# main.net
KiCad netlist of a schematic drawn in EAGLE
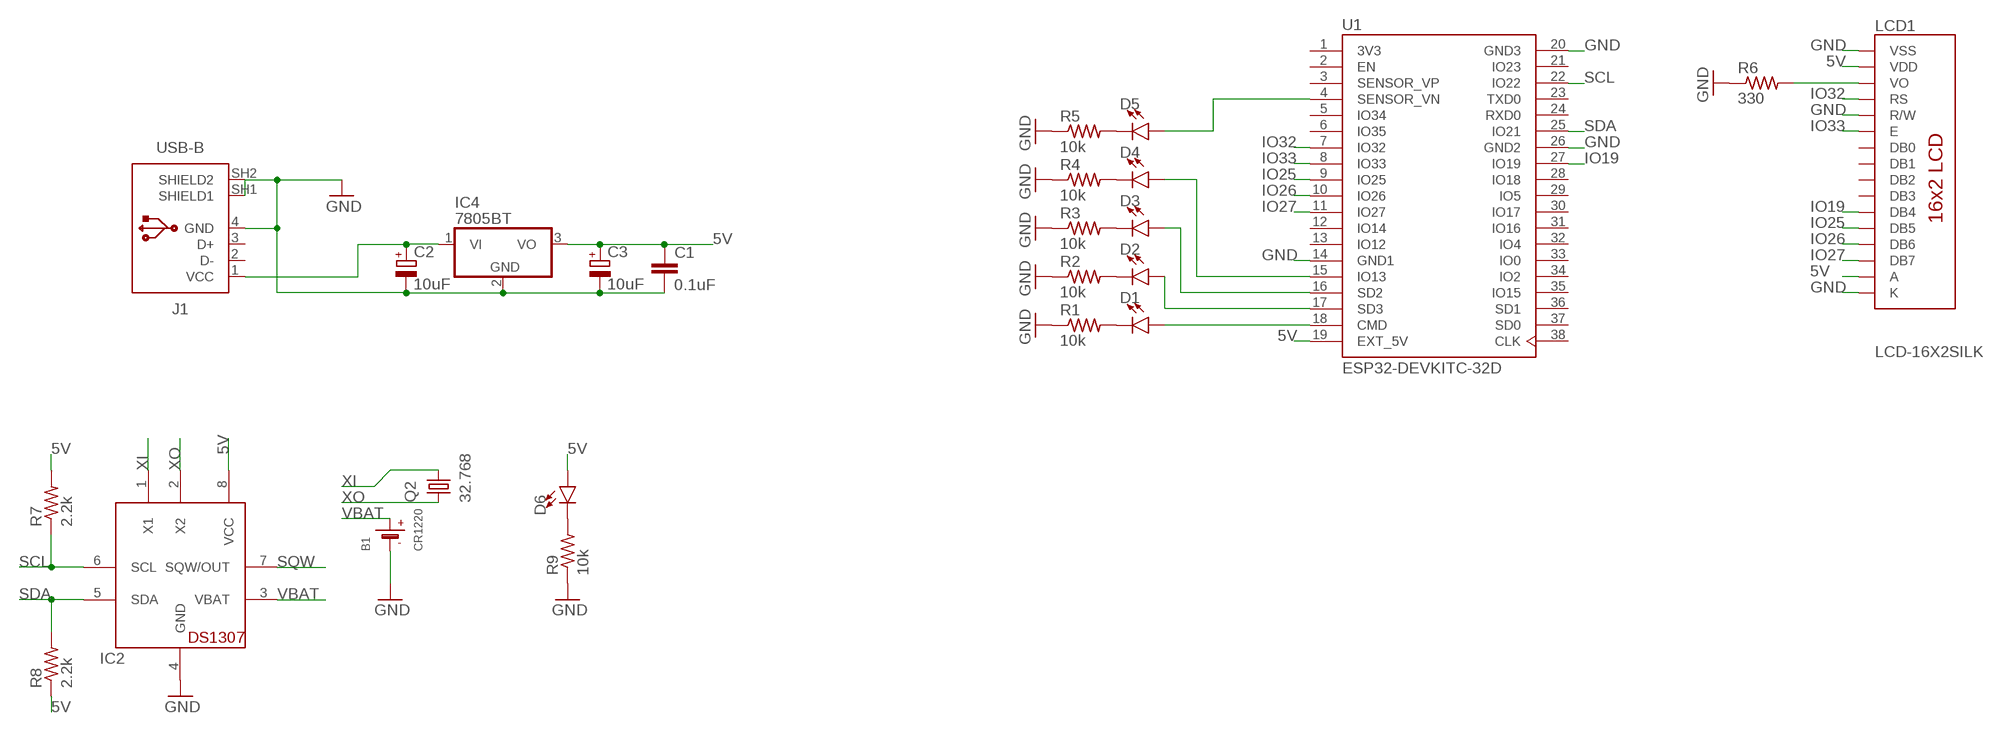
[diagram p0: schematic, sheet 1]

(export (version "E")
  (design (tool "Eeschema 10.0.6"))
  (components
    (comp (ref "B1")
      (value "CR1220")
      (footprint "eagle-import:CR1220")
      (libsource (lib "eagle-import") (part "BATTERYCR1220_SMT"))
    )
    (comp (ref "C1")
      (value "0.1uF")
      (footprint "eagle-import:C050-024X044")
      (libsource (lib "eagle-import") (part "C-EU050-024X044"))
    )
    (comp (ref "C2")
      (value "10uF")
      (footprint "eagle-import:E2-5")
      (libsource (lib "eagle-import") (part "CPOL-EUE2-5"))
    )
    (comp (ref "C3")
      (value "10uF")
      (footprint "eagle-import:E2-5")
      (libsource (lib "eagle-import") (part "CPOL-EUE2-5"))
    )
    (comp (ref "D1")
      (value "LED5MM")
      (footprint "eagle-import:LED_5MM")
      (libsource (lib "eagle-import") (part "LED5MM"))
    )
    (comp (ref "D2")
      (value "LED5MM")
      (footprint "eagle-import:LED_5MM")
      (libsource (lib "eagle-import") (part "LED5MM"))
    )
    (comp (ref "D3")
      (value "LED5MM")
      (footprint "eagle-import:LED_5MM")
      (libsource (lib "eagle-import") (part "LED5MM"))
    )
    (comp (ref "D4")
      (value "LED5MM")
      (footprint "eagle-import:LED_5MM")
      (libsource (lib "eagle-import") (part "LED5MM"))
    )
    (comp (ref "D5")
      (value "LED5MM")
      (footprint "eagle-import:LED_5MM")
      (libsource (lib "eagle-import") (part "LED5MM"))
    )
    (comp (ref "D6")
      (value "LED5MM")
      (footprint "eagle-import:LED_5MM")
      (libsource (lib "eagle-import") (part "LED5MM"))
    )
    (comp (ref "IC2")
      (value "DS1307")
      (footprint "eagle-import:DIL08")
      (libsource (lib "eagle-import") (part "DS1307"))
    )
    (comp (ref "IC4")
      (value "7805BT")
      (footprint "eagle-import:TO220V")
      (libsource (lib "eagle-import") (part "78TV05"))
    )
    (comp (ref "J1")
      (value "USB-B")
      (footprint "eagle-import:61729-1011BLF")
      (fields (field (name "MANUFACTURER") "Amphenol ICC (FCI)") (field (name "MPN") "61729-1011BLF"))
      (libsource (lib "eagle-import") (part "61729-1011"))
    )
    (comp (ref "LCD1")
      (value "LCD-16X2SILK")
      (footprint "eagle-import:LCD-16X2")
      (libsource (lib "eagle-import") (part "LCD-16X2SILK"))
    )
    (comp (ref "Q2")
      (value "32.768")
      (footprint "eagle-import:TC26V")
      (libsource (lib "eagle-import") (part "CRYSTALTC26V"))
    )
    (comp (ref "R1")
      (value "10k")
      (footprint "eagle-import:0207_7")
      (libsource (lib "eagle-import") (part "R-US_0207/7"))
    )
    (comp (ref "R2")
      (value "10k")
      (footprint "eagle-import:0207_7")
      (libsource (lib "eagle-import") (part "R-US_0207/7"))
    )
    (comp (ref "R3")
      (value "10k")
      (footprint "eagle-import:0207_7")
      (libsource (lib "eagle-import") (part "R-US_0207/7"))
    )
    (comp (ref "R4")
      (value "10k")
      (footprint "eagle-import:0207_7")
      (libsource (lib "eagle-import") (part "R-US_0207/7"))
    )
    (comp (ref "R5")
      (value "10k")
      (footprint "eagle-import:0207_7")
      (libsource (lib "eagle-import") (part "R-US_0207/7"))
    )
    (comp (ref "R6")
      (value "330")
      (footprint "eagle-import:0207_7")
      (libsource (lib "eagle-import") (part "R-US_0207/7"))
    )
    (comp (ref "R7")
      (value "2.2k")
      (footprint "eagle-import:0207_7")
      (libsource (lib "eagle-import") (part "R-US_0207/7"))
    )
    (comp (ref "R8")
      (value "2.2k")
      (footprint "eagle-import:0207_7")
      (libsource (lib "eagle-import") (part "R-US_0207/7"))
    )
    (comp (ref "R9")
      (value "10k")
      (footprint "eagle-import:0207_7")
      (libsource (lib "eagle-import") (part "R-US_0207/7"))
    )
    (comp (ref "U1")
      (value "ESP32-DEVKITC-32D")
      (footprint "eagle-import:MODULE_ESP32-DEVKITC-32D")
      (fields (field (name "MF") "Espressif Systems"))
      (libsource (lib "eagle-import") (part "ESP32-DEVKITC-32D"))
    )
  )
  (nets
    (net (code "1") (name "/3V3") (class "Default")
      (node (ref "U1") (pin "1") (pinfunction "3V3_1") (pintype "power_in"))
    )
    (net (code "2") (name "/5V") (class "Default")
      (node (ref "C1") (pin "1") (pinfunction "1_1") (pintype "passive"))
      (node (ref "C3") (pin "+") (pinfunction "+_+") (pintype "passive"))
      (node (ref "D6") (pin "A") (pinfunction "A_A") (pintype "passive"))
      (node (ref "IC2") (pin "8") (pinfunction "VCC_8") (pintype "power_in"))
      (node (ref "IC4") (pin "3") (pinfunction "VO_3") (pintype "passive"))
      (node (ref "LCD1") (pin "15") (pinfunction "A_15") (pintype "power_in"))
      (node (ref "LCD1") (pin "2") (pinfunction "VDD_2") (pintype "power_in"))
      (node (ref "R7") (pin "2") (pinfunction "2_2") (pintype "passive"))
      (node (ref "R8") (pin "1") (pinfunction "1_1") (pintype "passive"))
      (node (ref "U1") (pin "19") (pinfunction "EXT_5V_19") (pintype "power_in"))
    )
    (net (code "3") (name "/IO19") (class "Default")
      (node (ref "LCD1") (pin "11") (pinfunction "DB4_11") (pintype "bidirectional"))
      (node (ref "U1") (pin "27") (pinfunction "IO19_27") (pintype "bidirectional"))
    )
    (net (code "4") (name "/IO25") (class "Default")
      (node (ref "LCD1") (pin "12") (pinfunction "DB5_12") (pintype "bidirectional"))
      (node (ref "U1") (pin "9") (pinfunction "IO25_9") (pintype "bidirectional"))
    )
    (net (code "5") (name "/IO26") (class "Default")
      (node (ref "LCD1") (pin "13") (pinfunction "DB6_13") (pintype "bidirectional"))
      (node (ref "U1") (pin "10") (pinfunction "IO26_10") (pintype "bidirectional"))
    )
    (net (code "6") (name "/IO27") (class "Default")
      (node (ref "LCD1") (pin "14") (pinfunction "DB7_14") (pintype "bidirectional"))
      (node (ref "U1") (pin "11") (pinfunction "IO27_11") (pintype "bidirectional"))
    )
    (net (code "7") (name "/IO32") (class "Default")
      (node (ref "LCD1") (pin "4") (pinfunction "RS_4") (pintype "input"))
      (node (ref "U1") (pin "7") (pinfunction "IO32_7") (pintype "bidirectional"))
    )
    (net (code "8") (name "/IO33") (class "Default")
      (node (ref "LCD1") (pin "6") (pinfunction "E_6") (pintype "input"))
      (node (ref "U1") (pin "8") (pinfunction "IO33_8") (pintype "bidirectional"))
    )
    (net (code "9") (name "/SCL") (class "Default")
      (node (ref "IC2") (pin "6") (pinfunction "SCL_6") (pintype "bidirectional"))
      (node (ref "R7") (pin "1") (pinfunction "1_1") (pintype "passive"))
      (node (ref "U1") (pin "22") (pinfunction "IO22_22") (pintype "bidirectional"))
    )
    (net (code "10") (name "/SDA") (class "Default")
      (node (ref "IC2") (pin "5") (pinfunction "SDA_5") (pintype "bidirectional"))
      (node (ref "R8") (pin "2") (pinfunction "2_2") (pintype "passive"))
      (node (ref "U1") (pin "25") (pinfunction "IO21_25") (pintype "bidirectional"))
    )
    (net (code "11") (name "/SQW") (class "Default")
      (node (ref "IC2") (pin "7") (pinfunction "SQW/OUT_7") (pintype "bidirectional"))
    )
    (net (code "12") (name "/VBAT") (class "Default")
      (node (ref "B1") (pin "+$1") (pinfunction "+_+$1") (pintype "passive"))
      (node (ref "IC2") (pin "3") (pinfunction "VBAT_3") (pintype "power_in"))
    )
    (net (code "13") (name "/XI") (class "Default")
      (node (ref "IC2") (pin "1") (pinfunction "X1_1") (pintype "passive"))
      (node (ref "Q2") (pin "2") (pinfunction "2_2") (pintype "passive"))
    )
    (net (code "14") (name "/XO") (class "Default")
      (node (ref "IC2") (pin "2") (pinfunction "X2_2") (pintype "passive"))
      (node (ref "Q2") (pin "1") (pinfunction "1_1") (pintype "passive"))
    )
    (net (code "15") (name "GND") (class "Default")
      (node (ref "B1") (pin "-") (pinfunction "-_-") (pintype "passive"))
      (node (ref "C1") (pin "2") (pinfunction "2_2") (pintype "passive"))
      (node (ref "C2") (pin "-") (pinfunction "-_-") (pintype "passive"))
      (node (ref "C3") (pin "-") (pinfunction "-_-") (pintype "passive"))
      (node (ref "IC2") (pin "4") (pinfunction "GND_4") (pintype "power_in"))
      (node (ref "IC4") (pin "2") (pinfunction "GND_2") (pintype "passive"))
      (node (ref "J1") (pin "4") (pinfunction "GND_4") (pintype "power_in"))
      (node (ref "J1") (pin "SH1") (pinfunction "SHIELD1_SH1") (pintype "power_in"))
      (node (ref "J1") (pin "SH2") (pinfunction "SHIELD2_SH2") (pintype "power_in"))
      (node (ref "LCD1") (pin "1") (pinfunction "VSS_1") (pintype "power_in"))
      (node (ref "LCD1") (pin "16") (pinfunction "K_16") (pintype "power_in"))
      (node (ref "LCD1") (pin "5") (pinfunction "R/W_5") (pintype "input"))
      (node (ref "R1") (pin "1") (pinfunction "1_1") (pintype "passive"))
      (node (ref "R2") (pin "1") (pinfunction "1_1") (pintype "passive"))
      (node (ref "R3") (pin "1") (pinfunction "1_1") (pintype "passive"))
      (node (ref "R4") (pin "1") (pinfunction "1_1") (pintype "passive"))
      (node (ref "R5") (pin "1") (pinfunction "1_1") (pintype "passive"))
      (node (ref "R6") (pin "1") (pinfunction "1_1") (pintype "passive"))
      (node (ref "R9") (pin "1") (pinfunction "1_1") (pintype "passive"))
      (node (ref "U1") (pin "14") (pinfunction "GND1_14") (pintype "power_in"))
      (node (ref "U1") (pin "20") (pinfunction "GND3_20") (pintype "power_in"))
      (node (ref "U1") (pin "26") (pinfunction "GND2_26") (pintype "power_in"))
    )
    (net (code "16") (name "Net-(D1-C)") (class "Default")
      (node (ref "D1") (pin "K") (pinfunction "C_K") (pintype "passive"))
      (node (ref "R1") (pin "2") (pinfunction "2_2") (pintype "passive"))
    )
    (net (code "17") (name "Net-(D2-C)") (class "Default")
      (node (ref "D2") (pin "K") (pinfunction "C_K") (pintype "passive"))
      (node (ref "R2") (pin "2") (pinfunction "2_2") (pintype "passive"))
    )
    (net (code "18") (name "Net-(D3-C)") (class "Default")
      (node (ref "D3") (pin "K") (pinfunction "C_K") (pintype "passive"))
      (node (ref "R3") (pin "2") (pinfunction "2_2") (pintype "passive"))
    )
    (net (code "19") (name "Net-(D4-C)") (class "Default")
      (node (ref "D4") (pin "K") (pinfunction "C_K") (pintype "passive"))
      (node (ref "R4") (pin "2") (pinfunction "2_2") (pintype "passive"))
    )
    (net (code "20") (name "Net-(D5-C)") (class "Default")
      (node (ref "D5") (pin "K") (pinfunction "C_K") (pintype "passive"))
      (node (ref "R5") (pin "2") (pinfunction "2_2") (pintype "passive"))
    )
    (net (code "21") (name "Net-(D6-C)") (class "Default")
      (node (ref "D6") (pin "K") (pinfunction "C_K") (pintype "passive"))
      (node (ref "R9") (pin "2") (pinfunction "2_2") (pintype "passive"))
    )
    (net (code "22") (name "Net-(IC4-VI)") (class "Default")
      (node (ref "C2") (pin "+") (pinfunction "+_+") (pintype "passive"))
      (node (ref "IC4") (pin "1") (pinfunction "VI_1") (pintype "input"))
      (node (ref "J1") (pin "1") (pinfunction "VCC_1") (pintype "power_in"))
    )
    (net (code "23") (name "Net-(LCD1-VO)") (class "Default")
      (node (ref "LCD1") (pin "3") (pinfunction "VO_3") (pintype "bidirectional"))
      (node (ref "R6") (pin "2") (pinfunction "2_2") (pintype "passive"))
    )
    (net (code "24") (name "Net-(U1-CMD)") (class "Default")
      (node (ref "D1") (pin "A") (pinfunction "A_A") (pintype "passive"))
      (node (ref "U1") (pin "18") (pinfunction "CMD_18") (pintype "bidirectional"))
    )
    (net (code "25") (name "Net-(U1-IO13)") (class "Default")
      (node (ref "D4") (pin "A") (pinfunction "A_A") (pintype "passive"))
      (node (ref "U1") (pin "15") (pinfunction "IO13_15") (pintype "bidirectional"))
    )
    (net (code "26") (name "Net-(U1-SD2)") (class "Default")
      (node (ref "D3") (pin "A") (pinfunction "A_A") (pintype "passive"))
      (node (ref "U1") (pin "16") (pinfunction "SD2_16") (pintype "bidirectional"))
    )
    (net (code "27") (name "Net-(U1-SD3)") (class "Default")
      (node (ref "D2") (pin "A") (pinfunction "A_A") (pintype "passive"))
      (node (ref "U1") (pin "17") (pinfunction "SD3_17") (pintype "bidirectional"))
    )
    (net (code "28") (name "Net-(U1-SENSOR_VN)") (class "Default")
      (node (ref "D5") (pin "A") (pinfunction "A_A") (pintype "passive"))
      (node (ref "U1") (pin "4") (pinfunction "SENSOR_VN_4") (pintype "input"))
    )
    (net (code "29") (name "unconnected-(J1-D+-Pad3)") (class "Default")
      (node (ref "J1") (pin "3") (pinfunction "D+_3") (pintype "bidirectional"))
    )
    (net (code "30") (name "unconnected-(J1-D--Pad2)") (class "Default")
      (node (ref "J1") (pin "2") (pinfunction "D-_2") (pintype "bidirectional"))
    )
    (net (code "31") (name "unconnected-(LCD1-DB0-Pad7)") (class "Default")
      (node (ref "LCD1") (pin "7") (pinfunction "DB0_7") (pintype "bidirectional"))
    )
    (net (code "32") (name "unconnected-(LCD1-DB1-Pad8)") (class "Default")
      (node (ref "LCD1") (pin "8") (pinfunction "DB1_8") (pintype "bidirectional"))
    )
    (net (code "33") (name "unconnected-(LCD1-DB2-Pad9)") (class "Default")
      (node (ref "LCD1") (pin "9") (pinfunction "DB2_9") (pintype "bidirectional"))
    )
    (net (code "34") (name "unconnected-(LCD1-DB3-Pad10)") (class "Default")
      (node (ref "LCD1") (pin "10") (pinfunction "DB3_10") (pintype "bidirectional"))
    )
    (net (code "35") (name "unconnected-(U1-CLK-Pad38)") (class "Default")
      (node (ref "U1") (pin "38") (pinfunction "CLK_38") (pintype "input"))
    )
    (net (code "36") (name "unconnected-(U1-EN-Pad2)") (class "Default")
      (node (ref "U1") (pin "2") (pinfunction "EN_2") (pintype "input"))
    )
    (net (code "37") (name "unconnected-(U1-IO0-Pad33)") (class "Default")
      (node (ref "U1") (pin "33") (pinfunction "IO0_33") (pintype "bidirectional"))
    )
    (net (code "38") (name "unconnected-(U1-IO2-Pad34)") (class "Default")
      (node (ref "U1") (pin "34") (pinfunction "IO2_34") (pintype "bidirectional"))
    )
    (net (code "39") (name "unconnected-(U1-IO4-Pad32)") (class "Default")
      (node (ref "U1") (pin "32") (pinfunction "IO4_32") (pintype "bidirectional"))
    )
    (net (code "40") (name "unconnected-(U1-IO5-Pad29)") (class "Default")
      (node (ref "U1") (pin "29") (pinfunction "IO5_29") (pintype "bidirectional"))
    )
    (net (code "41") (name "unconnected-(U1-IO12-Pad13)") (class "Default")
      (node (ref "U1") (pin "13") (pinfunction "IO12_13") (pintype "bidirectional"))
    )
    (net (code "42") (name "unconnected-(U1-IO14-Pad12)") (class "Default")
      (node (ref "U1") (pin "12") (pinfunction "IO14_12") (pintype "bidirectional"))
    )
    (net (code "43") (name "unconnected-(U1-IO15-Pad35)") (class "Default")
      (node (ref "U1") (pin "35") (pinfunction "IO15_35") (pintype "bidirectional"))
    )
    (net (code "44") (name "unconnected-(U1-IO16-Pad31)") (class "Default")
      (node (ref "U1") (pin "31") (pinfunction "IO16_31") (pintype "bidirectional"))
    )
    (net (code "45") (name "unconnected-(U1-IO17-Pad30)") (class "Default")
      (node (ref "U1") (pin "30") (pinfunction "IO17_30") (pintype "bidirectional"))
    )
    (net (code "46") (name "unconnected-(U1-IO18-Pad28)") (class "Default")
      (node (ref "U1") (pin "28") (pinfunction "IO18_28") (pintype "bidirectional"))
    )
    (net (code "47") (name "unconnected-(U1-IO23-Pad21)") (class "Default")
      (node (ref "U1") (pin "21") (pinfunction "IO23_21") (pintype "bidirectional"))
    )
    (net (code "48") (name "unconnected-(U1-IO34-Pad5)") (class "Default")
      (node (ref "U1") (pin "5") (pinfunction "IO34_5") (pintype "bidirectional"))
    )
    (net (code "49") (name "unconnected-(U1-IO35-Pad6)") (class "Default")
      (node (ref "U1") (pin "6") (pinfunction "IO35_6") (pintype "bidirectional"))
    )
    (net (code "50") (name "unconnected-(U1-RXD0-Pad24)") (class "Default")
      (node (ref "U1") (pin "24") (pinfunction "RXD0_24") (pintype "input"))
    )
    (net (code "51") (name "unconnected-(U1-SD0-Pad37)") (class "Default")
      (node (ref "U1") (pin "37") (pinfunction "SD0_37") (pintype "bidirectional"))
    )
    (net (code "52") (name "unconnected-(U1-SD1-Pad36)") (class "Default")
      (node (ref "U1") (pin "36") (pinfunction "SD1_36") (pintype "bidirectional"))
    )
    (net (code "53") (name "unconnected-(U1-SENSOR_VP-Pad3)") (class "Default")
      (node (ref "U1") (pin "3") (pinfunction "SENSOR_VP_3") (pintype "input"))
    )
    (net (code "54") (name "unconnected-(U1-TXD0-Pad23)") (class "Default")
      (node (ref "U1") (pin "23") (pinfunction "TXD0_23") (pintype "output"))
    )
  )
)
